# J3-3xGTHCLK_1xPLLCLK_MIO_B47_B48.net
KiCad netlist of a schematic drawn in Altium Designer
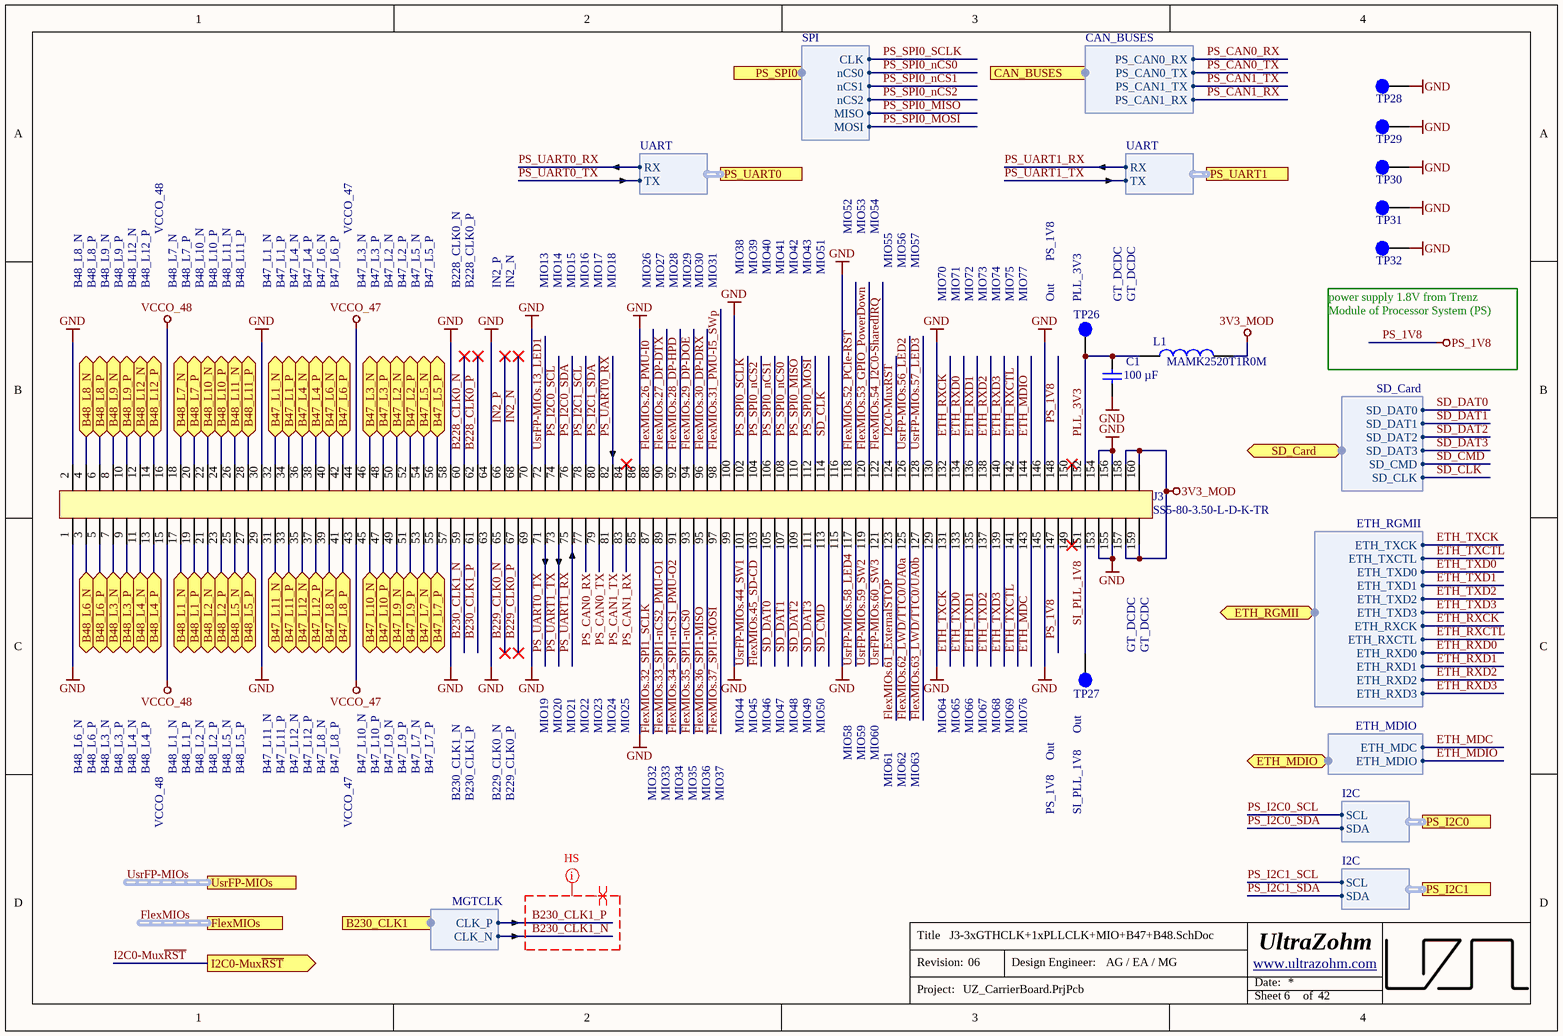
[diagram p0: J3-3xGTHCLK+1xPLLCLK+MIO+B47+B48.SchDoc]

(export (version "E")
  (design (tool "Eeschema 10.0.6"))
  (components
    (comp (ref "C1")
      (value "100 µF")
      (footprint "C_1206_TE")
      (description "6.3V 100uF X5R ±20% 1206 Multilayer Ceramic Capacitors MLCC")
      (fields
        (field (name "TOLERANCE") "20%")
        (field (name "MANUFACTURER PART NUMBER") "CL31A107MQHNNNE")
        (field (name "CREATED FROM") "MGeier")
      )
      (libsource (lib "user") (part "CAP-NP"))
    )
    (comp (ref "J3")
      (value "SS5-80-3.50-L-D-K-TR")
      (footprint "SS5-80-3.50-L-D-K-TR")
      (description "0.5 mm Ultra Fine Pitch Socket REF192552-01, 160 Pins")
      (fields
        (field (name "MANUFACTURER") "SAMTEC")
        (field (name "LCSC PART NUMBER") "C5292077")
        (field (name "CREATED FROM") "MGremer")
      )
      (libsource (lib "user") (part "SS5-80-3.50-L-D-K-TR"))
    )
    (comp (ref "L1")
      (value "MAMK2520T1R0M")
      (footprint "INDC2520X120N")
      (description "1uH @2MHz ±20%, 2.7A, 59mOhm, 5040")
      (fields
        (field (name "MF") "EPCOS / TDK")
        (field (name "MPN") "B82464G4154M")
        (field (name "CREATED FROM") "FRosner")
      )
      (libsource (lib "user") (part "B82464G4154M"))
    )
    (comp (ref "TP26") (value "Testpoint 1mm") (footprint "TP_1mm") (libsource (lib "TE") (part "TP")))
    (comp (ref "TP27") (value "Testpoint 1mm") (footprint "TP_1mm") (libsource (lib "TE") (part "TP")))
    (comp (ref "TP28") (value "Testpoint 1mm") (footprint "TP_1mm") (libsource (lib "TE") (part "TP")))
    (comp (ref "TP29") (value "Testpoint 1mm") (footprint "TP_1mm") (libsource (lib "TE") (part "TP")))
    (comp (ref "TP30") (value "Testpoint 1mm") (footprint "TP_1mm") (libsource (lib "TE") (part "TP")))
    (comp (ref "TP31") (value "Testpoint 1mm") (footprint "TP_1mm") (libsource (lib "TE") (part "TP")))
    (comp (ref "TP32") (value "Testpoint 1mm") (footprint "TP_1mm") (libsource (lib "TE") (part "TP")))
  )
  (nets
    (net (code "10") (name "/B47_L1_N") (class "Default")
      (node (ref "J3") (pin "32") (pinfunction "32_32") (pintype "passive"))
    )
    (net (code "11") (name "/B47_L1_P") (class "Default")
      (node (ref "J3") (pin "34") (pinfunction "34_34") (pintype "passive"))
    )
    (net (code "12") (name "/B47_L2_N") (class "Default")
      (node (ref "J3") (pin "50") (pinfunction "50_50") (pintype "passive"))
    )
    (net (code "13") (name "/B47_L2_P") (class "Default")
      (node (ref "J3") (pin "52") (pinfunction "52_52") (pintype "passive"))
    )
    (net (code "14") (name "/B47_L3_N") (class "Default")
      (node (ref "J3") (pin "46") (pinfunction "46_46") (pintype "passive"))
    )
    (net (code "15") (name "/B47_L3_P") (class "Default")
      (node (ref "J3") (pin "48") (pinfunction "48_48") (pintype "passive"))
    )
    (net (code "16") (name "/B47_L4_N") (class "Default")
      (node (ref "J3") (pin "36") (pinfunction "36_36") (pintype "passive"))
    )
    (net (code "17") (name "/B47_L4_P") (class "Default")
      (node (ref "J3") (pin "38") (pinfunction "38_38") (pintype "passive"))
    )
    (net (code "18") (name "/B47_L5_N") (class "Default")
      (node (ref "J3") (pin "54") (pinfunction "54_54") (pintype "passive"))
    )
    (net (code "19") (name "/B47_L5_P") (class "Default")
      (node (ref "J3") (pin "56") (pinfunction "56_56") (pintype "passive"))
    )
    (net (code "20") (name "/B47_L6_N") (class "Default")
      (node (ref "J3") (pin "40") (pinfunction "40_40") (pintype "passive"))
    )
    (net (code "21") (name "/B47_L6_P") (class "Default")
      (node (ref "J3") (pin "42") (pinfunction "42_42") (pintype "passive"))
    )
    (net (code "22") (name "/B47_L7_N") (class "Default")
      (node (ref "J3") (pin "53") (pinfunction "53_53") (pintype "passive"))
    )
    (net (code "23") (name "/B47_L7_P") (class "Default")
      (node (ref "J3") (pin "55") (pinfunction "55_55") (pintype "passive"))
    )
    (net (code "24") (name "/B47_L8_N") (class "Default")
      (node (ref "J3") (pin "39") (pinfunction "39_39") (pintype "passive"))
    )
    (net (code "25") (name "/B47_L8_P") (class "Default")
      (node (ref "J3") (pin "41") (pinfunction "41_41") (pintype "passive"))
    )
    (net (code "26") (name "/B47_L9_N") (class "Default")
      (node (ref "J3") (pin "49") (pinfunction "49_49") (pintype "passive"))
    )
    (net (code "27") (name "/B47_L9_P") (class "Default")
      (node (ref "J3") (pin "51") (pinfunction "51_51") (pintype "passive"))
    )
    (net (code "28") (name "/B47_L10_N") (class "Default")
      (node (ref "J3") (pin "45") (pinfunction "45_45") (pintype "passive"))
    )
    (net (code "29") (name "/B47_L10_P") (class "Default")
      (node (ref "J3") (pin "47") (pinfunction "47_47") (pintype "passive"))
    )
    (net (code "30") (name "/B47_L11_N") (class "Default")
      (node (ref "J3") (pin "31") (pinfunction "31_31") (pintype "passive"))
    )
    (net (code "31") (name "/B47_L11_P") (class "Default")
      (node (ref "J3") (pin "33") (pinfunction "33_33") (pintype "passive"))
    )
    (net (code "32") (name "/B47_L12_N") (class "Default")
      (node (ref "J3") (pin "35") (pinfunction "35_35") (pintype "passive"))
    )
    (net (code "33") (name "/B47_L12_P") (class "Default")
      (node (ref "J3") (pin "37") (pinfunction "37_37") (pintype "passive"))
    )
    (net (code "34") (name "/B48_L1_N") (class "Default")
      (node (ref "J3") (pin "17") (pinfunction "17_17") (pintype "passive"))
    )
    (net (code "35") (name "/B48_L1_P") (class "Default")
      (node (ref "J3") (pin "19") (pinfunction "19_19") (pintype "passive"))
    )
    (net (code "36") (name "/B48_L2_N") (class "Default")
      (node (ref "J3") (pin "21") (pinfunction "21_21") (pintype "passive"))
    )
    (net (code "37") (name "/B48_L2_P") (class "Default")
      (node (ref "J3") (pin "23") (pinfunction "23_23") (pintype "passive"))
    )
    (net (code "38") (name "/B48_L3_N") (class "Default")
      (node (ref "J3") (pin "7") (pinfunction "7_7") (pintype "passive"))
    )
    (net (code "39") (name "/B48_L3_P") (class "Default")
      (node (ref "J3") (pin "9") (pinfunction "9_9") (pintype "passive"))
    )
    (net (code "40") (name "/B48_L4_N") (class "Default")
      (node (ref "J3") (pin "11") (pinfunction "11_11") (pintype "passive"))
    )
    (net (code "41") (name "/B48_L4_P") (class "Default")
      (node (ref "J3") (pin "13") (pinfunction "13_13") (pintype "passive"))
    )
    (net (code "42") (name "/B48_L5_N") (class "Default")
      (node (ref "J3") (pin "25") (pinfunction "25_25") (pintype "passive"))
    )
    (net (code "43") (name "/B48_L5_P") (class "Default")
      (node (ref "J3") (pin "27") (pinfunction "27_27") (pintype "passive"))
    )
    (net (code "44") (name "/B48_L6_N") (class "Default")
      (node (ref "J3") (pin "3") (pinfunction "3_3") (pintype "passive"))
    )
    (net (code "45") (name "/B48_L6_P") (class "Default")
      (node (ref "J3") (pin "5") (pinfunction "5_5") (pintype "passive"))
    )
    (net (code "46") (name "/B48_L7_N") (class "Default")
      (node (ref "J3") (pin "18") (pinfunction "18_18") (pintype "passive"))
    )
    (net (code "47") (name "/B48_L7_P") (class "Default")
      (node (ref "J3") (pin "20") (pinfunction "20_20") (pintype "passive"))
    )
    (net (code "48") (name "/B48_L8_N") (class "Default")
      (node (ref "J3") (pin "4") (pinfunction "4_4") (pintype "passive"))
    )
    (net (code "49") (name "/B48_L8_P") (class "Default")
      (node (ref "J3") (pin "6") (pinfunction "6_6") (pintype "passive"))
    )
    (net (code "50") (name "/B48_L9_N") (class "Default")
      (node (ref "J3") (pin "8") (pinfunction "8_8") (pintype "passive"))
    )
    (net (code "51") (name "/B48_L9_P") (class "Default")
      (node (ref "J3") (pin "10") (pinfunction "10_10") (pintype "passive"))
    )
    (net (code "52") (name "/B48_L10_N") (class "Default")
      (node (ref "J3") (pin "22") (pinfunction "22_22") (pintype "passive"))
    )
    (net (code "53") (name "/B48_L10_P") (class "Default")
      (node (ref "J3") (pin "24") (pinfunction "24_24") (pintype "passive"))
    )
    (net (code "54") (name "/B48_L11_N") (class "Default")
      (node (ref "J3") (pin "26") (pinfunction "26_26") (pintype "passive"))
    )
    (net (code "55") (name "/B48_L11_P") (class "Default")
      (node (ref "J3") (pin "28") (pinfunction "28_28") (pintype "passive"))
    )
    (net (code "56") (name "/B48_L12_N") (class "Default")
      (node (ref "J3") (pin "12") (pinfunction "12_12") (pintype "passive"))
    )
    (net (code "57") (name "/B48_L12_P") (class "Default")
      (node (ref "J3") (pin "14") (pinfunction "14_14") (pintype "passive"))
    )
    (net (code "58") (name "/B228_CLK0_N") (class "Default")
      (node (ref "J3") (pin "60") (pinfunction "60_60") (pintype "passive+no_connect"))
    )
    (net (code "59") (name "/B228_CLK0_P") (class "Default")
      (node (ref "J3") (pin "62") (pinfunction "62_62") (pintype "passive+no_connect"))
    )
    (net (code "60") (name "/B229_CLK0_N") (class "Default")
      (node (ref "J3") (pin "65") (pinfunction "65_65") (pintype "passive+no_connect"))
    )
    (net (code "61") (name "/B229_CLK0_P") (class "Default")
      (node (ref "J3") (pin "67") (pinfunction "67_67") (pintype "passive+no_connect"))
    )
    (net (code "62") (name "/B230_CLK1_N") (class "Default")
      (node (ref "J3") (pin "59") (pinfunction "59_59") (pintype "passive"))
    )
    (net (code "63") (name "/B230_CLK1_P") (class "Default")
      (node (ref "J3") (pin "61") (pinfunction "61_61") (pintype "passive"))
    )
    (net (code "64") (name "/ETH_MDC") (class "Default")
      (node (ref "J3") (pin "143") (pinfunction "143_143") (pintype "passive"))
    )
    (net (code "65") (name "/ETH_MDIO") (class "Default")
      (node (ref "J3") (pin "144") (pinfunction "144_144") (pintype "passive"))
    )
    (net (code "66") (name "/ETH_RXCK") (class "Default")
      (node (ref "J3") (pin "132") (pinfunction "132_132") (pintype "passive"))
    )
    (net (code "67") (name "/ETH_RXCTL") (class "Default")
      (node (ref "J3") (pin "142") (pinfunction "142_142") (pintype "passive"))
    )
    (net (code "68") (name "/ETH_RXD0") (class "Default")
      (node (ref "J3") (pin "134") (pinfunction "134_134") (pintype "passive"))
    )
    (net (code "69") (name "/ETH_RXD1") (class "Default")
      (node (ref "J3") (pin "136") (pinfunction "136_136") (pintype "passive"))
    )
    (net (code "70") (name "/ETH_RXD2") (class "Default")
      (node (ref "J3") (pin "138") (pinfunction "138_138") (pintype "passive"))
    )
    (net (code "71") (name "/ETH_RXD3") (class "Default")
      (node (ref "J3") (pin "140") (pinfunction "140_140") (pintype "passive"))
    )
    (net (code "72") (name "/ETH_TXCK") (class "Default")
      (node (ref "J3") (pin "131") (pinfunction "131_131") (pintype "passive"))
    )
    (net (code "73") (name "/ETH_TXCTL") (class "Default")
      (node (ref "J3") (pin "141") (pinfunction "141_141") (pintype "passive"))
    )
    (net (code "74") (name "/ETH_TXD0") (class "Default")
      (node (ref "J3") (pin "133") (pinfunction "133_133") (pintype "passive"))
    )
    (net (code "75") (name "/ETH_TXD1") (class "Default")
      (node (ref "J3") (pin "135") (pinfunction "135_135") (pintype "passive"))
    )
    (net (code "76") (name "/ETH_TXD2") (class "Default")
      (node (ref "J3") (pin "137") (pinfunction "137_137") (pintype "passive"))
    )
    (net (code "77") (name "/ETH_TXD3") (class "Default")
      (node (ref "J3") (pin "139") (pinfunction "139_139") (pintype "passive"))
    )
    (net (code "78") (name "/FlexMIOs.26_PMU-I0") (class "Default")
      (node (ref "J3") (pin "88") (pinfunction "88_88") (pintype "passive"))
    )
    (net (code "79") (name "/FlexMIOs.27_DP-DTX") (class "Default")
      (node (ref "J3") (pin "90") (pinfunction "90_90") (pintype "passive"))
    )
    (net (code "80") (name "/FlexMIOs.28_DP-HPD") (class "Default")
      (node (ref "J3") (pin "92") (pinfunction "92_92") (pintype "passive"))
    )
    (net (code "81") (name "/FlexMIOs.29_DP-DOE") (class "Default")
      (node (ref "J3") (pin "94") (pinfunction "94_94") (pintype "passive"))
    )
    (net (code "82") (name "/FlexMIOs.30_DP-DRX") (class "Default")
      (node (ref "J3") (pin "96") (pinfunction "96_96") (pintype "passive"))
    )
    (net (code "83") (name "/FlexMIOs.31_PMU-I5_SWp") (class "Default")
      (node (ref "J3") (pin "98") (pinfunction "98_98") (pintype "passive"))
    )
    (net (code "84") (name "/FlexMIOs.32_SPI1_SCLK") (class "Default")
      (node (ref "J3") (pin "87") (pinfunction "87_87") (pintype "passive"))
    )
    (net (code "85") (name "/FlexMIOs.33_SPI1-nCS2_PMU-O1") (class "Default")
      (node (ref "J3") (pin "89") (pinfunction "89_89") (pintype "passive"))
    )
    (net (code "86") (name "/FlexMIOs.34_SPI1-nCS1_PMU-O2") (class "Default")
      (node (ref "J3") (pin "91") (pinfunction "91_91") (pintype "passive"))
    )
    (net (code "87") (name "/FlexMIOs.35_SPI1-nCS0") (class "Default")
      (node (ref "J3") (pin "93") (pinfunction "93_93") (pintype "passive"))
    )
    (net (code "88") (name "/FlexMIOs.36_SPI1-MISO") (class "Default")
      (node (ref "J3") (pin "95") (pinfunction "95_95") (pintype "passive"))
    )
    (net (code "89") (name "/FlexMIOs.37_SPI1-MOSI") (class "Default")
      (node (ref "J3") (pin "97") (pinfunction "97_97") (pintype "passive"))
    )
    (net (code "90") (name "/FlexMIOs.45_SD-CD") (class "Default")
      (node (ref "J3") (pin "103") (pinfunction "103_103") (pintype "passive"))
    )
    (net (code "91") (name "/FlexMIOs.52_PCIe-~{RST}") (class "Default")
      (node (ref "J3") (pin "118") (pinfunction "118_118") (pintype "passive"))
    )
    (net (code "92") (name "/FlexMIOs.53_GPIO_PowerDown") (class "Default")
      (node (ref "J3") (pin "120") (pinfunction "120_120") (pintype "passive"))
    )
    (net (code "93") (name "/FlexMIOs.54_I2C0-Shared~{IRQ}") (class "Default")
      (node (ref "J3") (pin "122") (pinfunction "122_122") (pintype "passive"))
    )
    (net (code "94") (name "/FlexMIOs.61_ExternalSTOP") (class "Default")
      (node (ref "J3") (pin "123") (pinfunction "123_123") (pintype "passive"))
    )
    (net (code "95") (name "/FlexMIOs.62_LWD{slash}TTC0{slash}UA0a") (class "Default")
      (node (ref "J3") (pin "125") (pinfunction "125_125") (pintype "passive"))
    )
    (net (code "96") (name "/FlexMIOs.63_LWD{slash}TTC0{slash}UA0b") (class "Default")
      (node (ref "J3") (pin "127") (pinfunction "127_127") (pintype "passive"))
    )
    (net (code "97") (name "/I2C0-Mux~{RST}") (class "Default")
      (node (ref "J3") (pin "124") (pinfunction "124_124") (pintype "passive"))
    )
    (net (code "98") (name "/IN2_N") (class "Default")
      (node (ref "J3") (pin "68") (pinfunction "68_68") (pintype "passive+no_connect"))
    )
    (net (code "99") (name "/IN2_P") (class "Default")
      (node (ref "J3") (pin "66") (pinfunction "66_66") (pintype "passive+no_connect"))
    )
    (net (code "100") (name "/PLL_3V3") (class "Default")
      (node (ref "C1") (pin "1") (pinfunction "1_1") (pintype "passive"))
      (node (ref "J3") (pin "152") (pinfunction "152_152") (pintype "passive"))
      (node (ref "L1") (pin "1") (pinfunction "1_1") (pintype "passive"))
      (node (ref "TP26") (pin "1") (pintype "passive"))
    )
    (net (code "101") (name "/PS_CAN0_RX") (class "Default")
      (node (ref "J3") (pin "77") (pinfunction "77_77") (pintype "passive"))
    )
    (net (code "102") (name "/PS_CAN0_TX") (class "Default")
      (node (ref "J3") (pin "79") (pinfunction "79_79") (pintype "passive"))
    )
    (net (code "103") (name "/PS_CAN1_RX") (class "Default")
      (node (ref "J3") (pin "83") (pinfunction "83_83") (pintype "passive"))
    )
    (net (code "104") (name "/PS_CAN1_TX") (class "Default")
      (node (ref "J3") (pin "81") (pinfunction "81_81") (pintype "passive"))
    )
    (net (code "105") (name "/PS_I2C0_SCL") (class "Default")
      (node (ref "J3") (pin "74") (pinfunction "74_74") (pintype "passive"))
    )
    (net (code "106") (name "/PS_I2C0_SDA") (class "Default")
      (node (ref "J3") (pin "76") (pinfunction "76_76") (pintype "passive"))
    )
    (net (code "107") (name "/PS_I2C1_SCL") (class "Default")
      (node (ref "J3") (pin "78") (pinfunction "78_78") (pintype "passive"))
    )
    (net (code "108") (name "/PS_I2C1_SDA") (class "Default")
      (node (ref "J3") (pin "80") (pinfunction "80_80") (pintype "passive"))
    )
    (net (code "109") (name "/PS_SPI0_MISO") (class "Default")
      (node (ref "J3") (pin "110") (pinfunction "110_110") (pintype "passive"))
    )
    (net (code "110") (name "/PS_SPI0_MOSI") (class "Default")
      (node (ref "J3") (pin "112") (pinfunction "112_112") (pintype "passive"))
    )
    (net (code "111") (name "/PS_SPI0_SCLK") (class "Default")
      (node (ref "J3") (pin "102") (pinfunction "102_102") (pintype "passive"))
    )
    (net (code "112") (name "/PS_SPI0_nCS0") (class "Default")
      (node (ref "J3") (pin "108") (pinfunction "108_108") (pintype "passive"))
    )
    (net (code "113") (name "/PS_SPI0_nCS1") (class "Default")
      (node (ref "J3") (pin "106") (pinfunction "106_106") (pintype "passive"))
    )
    (net (code "114") (name "/PS_SPI0_nCS2") (class "Default")
      (node (ref "J3") (pin "104") (pinfunction "104_104") (pintype "passive"))
    )
    (net (code "115") (name "/PS_UART0_RX") (class "Default")
      (node (ref "J3") (pin "82") (pinfunction "82_82") (pintype "passive"))
    )
    (net (code "116") (name "/PS_UART0_TX") (class "Default")
      (node (ref "J3") (pin "71") (pinfunction "71_71") (pintype "passive"))
    )
    (net (code "117") (name "/PS_UART1_RX") (class "Default")
      (node (ref "J3") (pin "75") (pinfunction "75_75") (pintype "passive"))
    )
    (net (code "118") (name "/PS_UART1_TX") (class "Default")
      (node (ref "J3") (pin "73") (pinfunction "73_73") (pintype "passive"))
    )
    (net (code "119") (name "/SD_CLK") (class "Default")
      (node (ref "J3") (pin "114") (pinfunction "114_114") (pintype "passive"))
    )
    (net (code "120") (name "/SD_CMD") (class "Default")
      (node (ref "J3") (pin "113") (pinfunction "113_113") (pintype "passive"))
    )
    (net (code "121") (name "/SD_DAT0") (class "Default")
      (node (ref "J3") (pin "105") (pinfunction "105_105") (pintype "passive"))
    )
    (net (code "122") (name "/SD_DAT1") (class "Default")
      (node (ref "J3") (pin "107") (pinfunction "107_107") (pintype "passive"))
    )
    (net (code "123") (name "/SD_DAT2") (class "Default")
      (node (ref "J3") (pin "109") (pinfunction "109_109") (pintype "passive"))
    )
    (net (code "124") (name "/SD_DAT3") (class "Default")
      (node (ref "J3") (pin "111") (pinfunction "111_111") (pintype "passive"))
    )
    (net (code "125") (name "/SI_PLL_1V8") (class "Default")
      (node (ref "J3") (pin "151") (pinfunction "151_151") (pintype "passive"))
      (node (ref "TP27") (pin "1") (pintype "passive"))
    )
    (net (code "126") (name "/UsrFP-MIOs.13_LED1") (class "Default")
      (node (ref "J3") (pin "72") (pinfunction "72_72") (pintype "passive"))
    )
    (net (code "127") (name "/UsrFP-MIOs.44_SW1") (class "Default")
      (node (ref "J3") (pin "101") (pinfunction "101_101") (pintype "passive"))
    )
    (net (code "128") (name "/UsrFP-MIOs.56_LED2") (class "Default")
      (node (ref "J3") (pin "126") (pinfunction "126_126") (pintype "passive"))
    )
    (net (code "129") (name "/UsrFP-MIOs.57_LED3") (class "Default")
      (node (ref "J3") (pin "128") (pinfunction "128_128") (pintype "passive"))
    )
    (net (code "130") (name "/UsrFP-MIOs.58_LED4") (class "Default")
      (node (ref "J3") (pin "117") (pinfunction "117_117") (pintype "passive"))
    )
    (net (code "131") (name "/UsrFP-MIOs.59_SW2") (class "Default")
      (node (ref "J3") (pin "119") (pinfunction "119_119") (pintype "passive"))
    )
    (net (code "132") (name "/UsrFP-MIOs.60_SW3") (class "Default")
      (node (ref "J3") (pin "121") (pinfunction "121_121") (pintype "passive"))
    )
    (net (code "143") (name "3V3_MOD") (class "Default")
      (node (ref "J3") (pin "157") (pinfunction "157_157") (pintype "passive"))
      (node (ref "J3") (pin "158") (pinfunction "158_158") (pintype "passive"))
      (node (ref "J3") (pin "159") (pinfunction "159_159") (pintype "passive"))
      (node (ref "J3") (pin "160") (pinfunction "160_160") (pintype "passive"))
      (node (ref "L1") (pin "2") (pinfunction "2_2") (pintype "passive"))
    )
    (net (code "144") (name "GND") (class "Default")
      (node (ref "C1") (pin "2") (pinfunction "2_2") (pintype "passive"))
      (node (ref "J3") (pin "1") (pinfunction "1_1") (pintype "passive"))
      (node (ref "J3") (pin "100") (pinfunction "100_100") (pintype "passive"))
      (node (ref "J3") (pin "115") (pinfunction "115_115") (pintype "passive"))
      (node (ref "J3") (pin "116") (pinfunction "116_116") (pintype "passive"))
      (node (ref "J3") (pin "129") (pinfunction "129_129") (pintype "passive"))
      (node (ref "J3") (pin "130") (pinfunction "130_130") (pintype "passive"))
      (node (ref "J3") (pin "145") (pinfunction "145_145") (pintype "passive"))
      (node (ref "J3") (pin "146") (pinfunction "146_146") (pintype "passive"))
      (node (ref "J3") (pin "153") (pinfunction "153_153") (pintype "passive"))
      (node (ref "J3") (pin "154") (pinfunction "154_154") (pintype "passive"))
      (node (ref "J3") (pin "155") (pinfunction "155_155") (pintype "passive"))
      (node (ref "J3") (pin "156") (pinfunction "156_156") (pintype "passive"))
      (node (ref "J3") (pin "2") (pinfunction "2_2") (pintype "passive"))
      (node (ref "J3") (pin "29") (pinfunction "29_29") (pintype "passive"))
      (node (ref "J3") (pin "30") (pinfunction "30_30") (pintype "passive"))
      (node (ref "J3") (pin "57") (pinfunction "57_57") (pintype "passive"))
      (node (ref "J3") (pin "58") (pinfunction "58_58") (pintype "passive"))
      (node (ref "J3") (pin "63") (pinfunction "63_63") (pintype "passive"))
      (node (ref "J3") (pin "64") (pinfunction "64_64") (pintype "passive"))
      (node (ref "J3") (pin "69") (pinfunction "69_69") (pintype "passive"))
      (node (ref "J3") (pin "70") (pinfunction "70_70") (pintype "passive"))
      (node (ref "J3") (pin "85") (pinfunction "85_85") (pintype "passive"))
      (node (ref "J3") (pin "86") (pinfunction "86_86") (pintype "passive"))
      (node (ref "J3") (pin "99") (pinfunction "99_99") (pintype "passive"))
      (node (ref "TP28") (pin "1") (pintype "passive"))
      (node (ref "TP29") (pin "1") (pintype "passive"))
      (node (ref "TP30") (pin "1") (pintype "passive"))
      (node (ref "TP31") (pin "1") (pintype "passive"))
      (node (ref "TP32") (pin "1") (pintype "passive"))
    )
    (net (code "145") (name "PS_1V8") (class "Default")
      (node (ref "J3") (pin "147") (pinfunction "147_147") (pintype "passive"))
      (node (ref "J3") (pin "148") (pinfunction "148_148") (pintype "passive"))
    )
    (net (code "146") (name "VCCO_47") (class "Default")
      (node (ref "J3") (pin "43") (pinfunction "43_43") (pintype "passive"))
      (node (ref "J3") (pin "44") (pinfunction "44_44") (pintype "passive"))
    )
    (net (code "147") (name "VCCO_48") (class "Default")
      (node (ref "J3") (pin "15") (pinfunction "15_15") (pintype "passive"))
      (node (ref "J3") (pin "16") (pinfunction "16_16") (pintype "passive"))
    )
    (net (code "148") (name "unconnected-(J3-Pad84)") (class "Default")
      (node (ref "J3") (pin "84") (pinfunction "84_84") (pintype "passive+no_connect"))
    )
    (net (code "149") (name "unconnected-(J3-Pad149)") (class "Default")
      (node (ref "J3") (pin "149") (pinfunction "149_149") (pintype "passive+no_connect"))
    )
    (net (code "150") (name "unconnected-(J3-Pad150)") (class "Default")
      (node (ref "J3") (pin "150") (pinfunction "150_150") (pintype "passive+no_connect"))
    )
  )
)
